# EEprom_Logger_V1.net
KiCad netlist of a schematic drawn in EAGLE
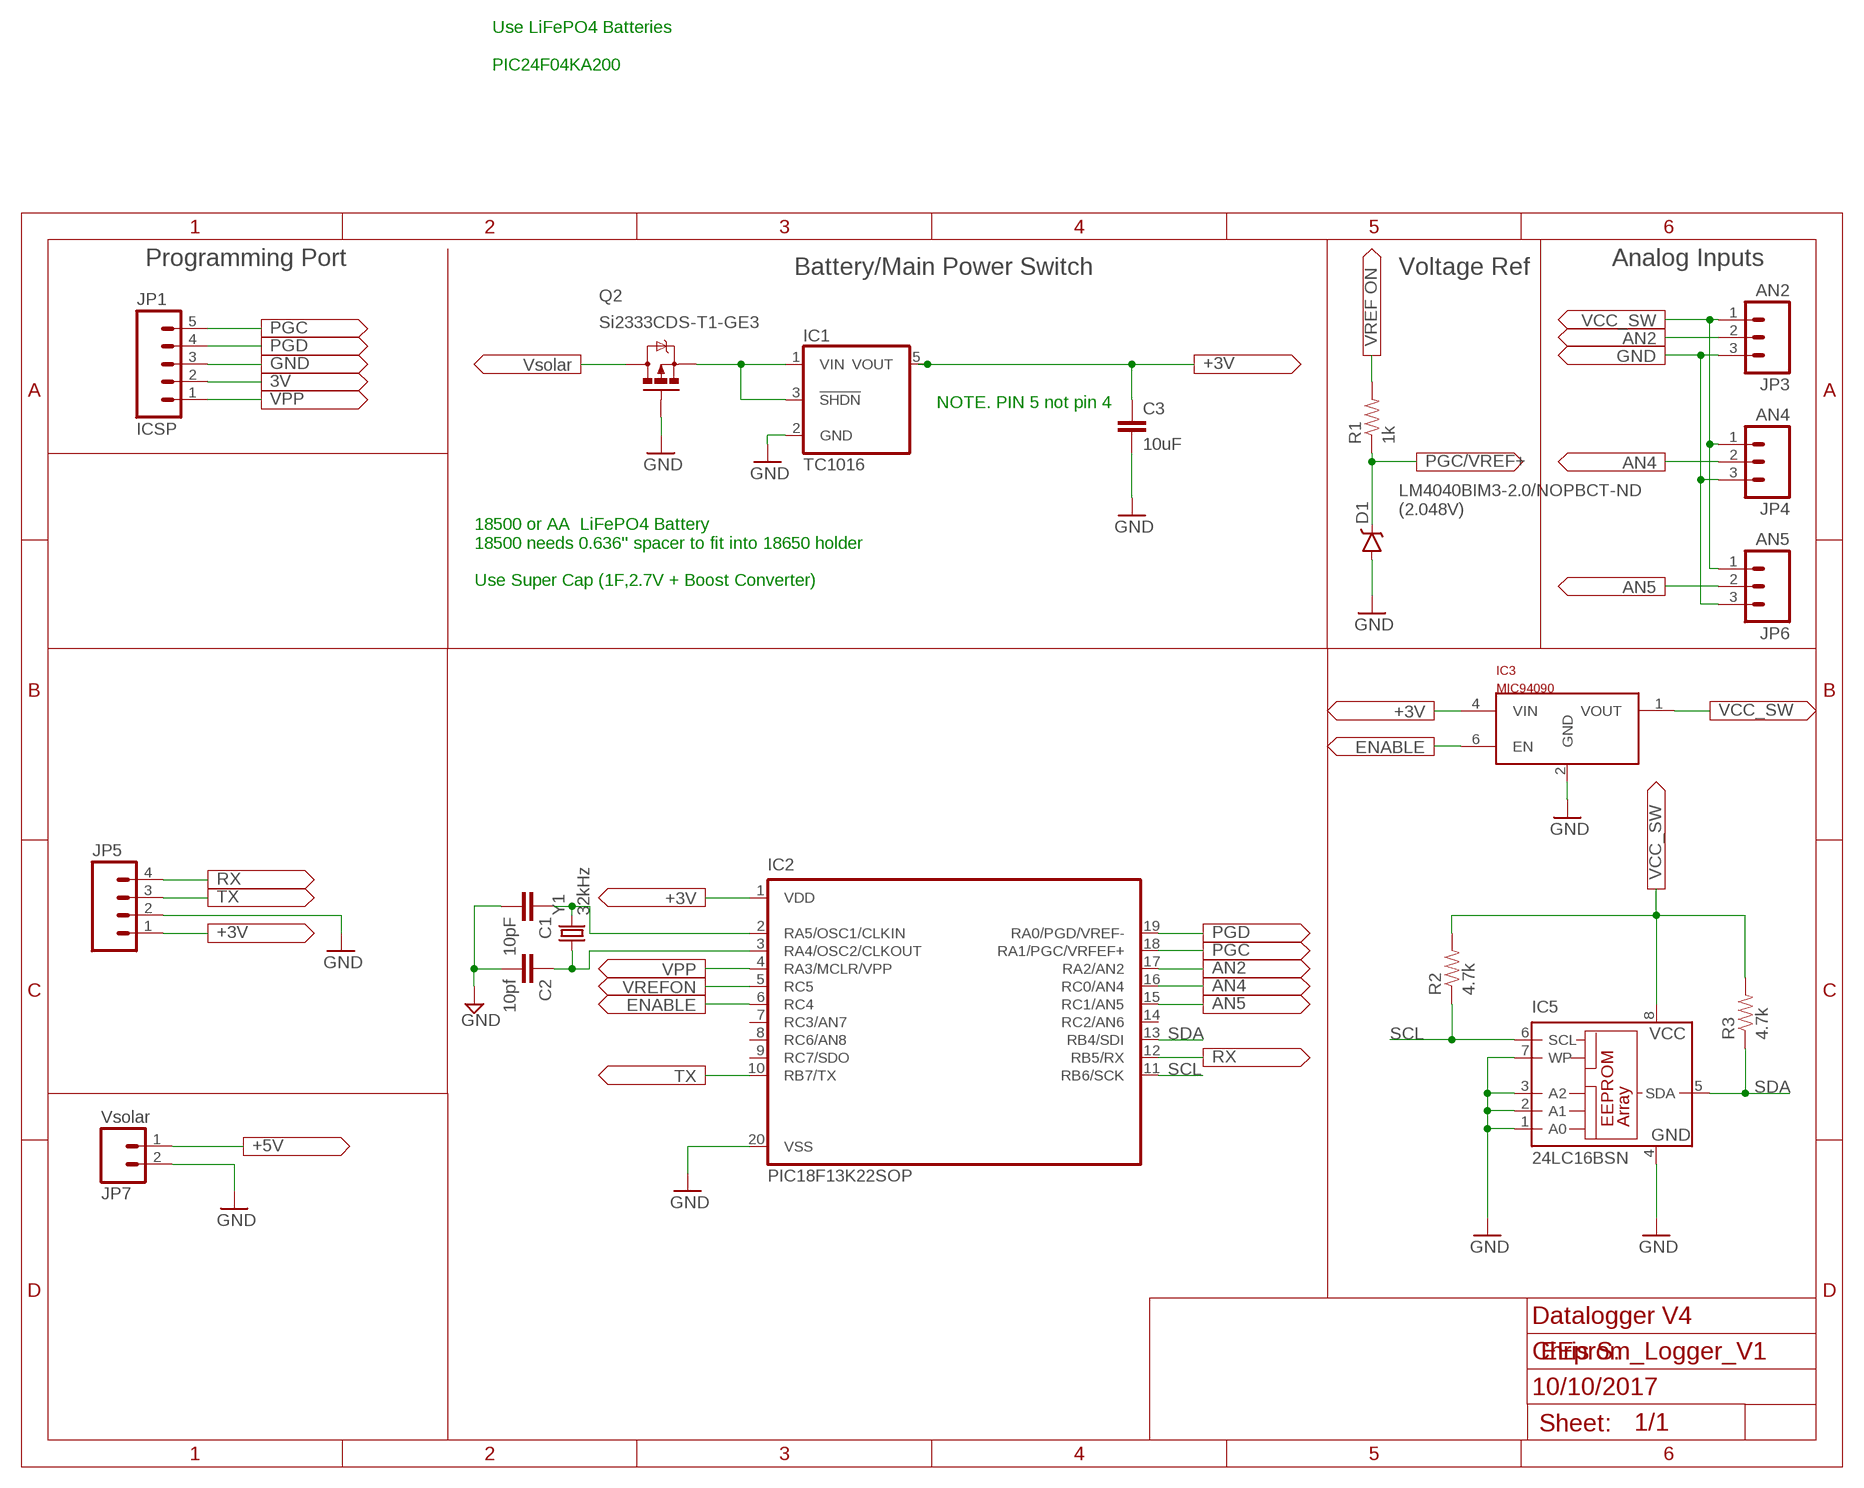
[diagram p0: schematic, sheet 1]

(export (version "E")
  (design (tool "Eeschema 10.0.6"))
  (components
    (comp (ref "C1")
      (value "10pF")
      (footprint "eagle-import:1206")
      (libsource (lib "eagle-import") (part "CAP1206"))
    )
    (comp (ref "C2")
      (value "10pf")
      (footprint "eagle-import:1206")
      (libsource (lib "eagle-import") (part "CAP1206"))
    )
    (comp (ref "C3")
      (value "10uF")
      (footprint "eagle-import:1206")
      (libsource (lib "eagle-import") (part "CAP1206"))
    )
    (comp (ref "D1")
      (value "V-REFERENCESMD")
      (footprint "eagle-import:SOT23-3")
      (libsource (lib "eagle-import") (part "V-REFERENCESMD"))
    )
    (comp (ref "IC1")
      (value "TC1016")
      (footprint "eagle-import:SOT23-5L")
      (libsource (lib "eagle-import") (part "TC1016"))
    )
    (comp (ref "IC2")
      (value "PIC18F13K22SOP")
      (footprint "eagle-import:SOP20W")
      (libsource (lib "eagle-import") (part "PIC18F13K22?SOP"))
    )
    (comp (ref "IC3")
      (value "MIC94090")
      (footprint "eagle-import:SC-70")
      (libsource (lib "eagle-import") (part "MIC94090"))
    )
    (comp (ref "IC5")
      (value "24LC16BSN")
      (footprint "eagle-import:SO-08")
      (fields (field (name "MF") "MICROCHIP") (field (name "MPN") "24LC16B/SN"))
      (libsource (lib "eagle-import") (part "24SNLC16B"))
    )
    (comp (ref "JP1")
      (value "ICSP")
      (footprint "eagle-import:1X05")
      (libsource (lib "eagle-import") (part "M05PTH"))
    )
    (comp (ref "JP3")
      (value "AN2")
      (footprint "eagle-import:JST-3-PTH")
      (libsource (lib "eagle-import") (part "M03JST-PTH"))
    )
    (comp (ref "JP4")
      (value "AN4")
      (footprint "eagle-import:JST-3-PTH")
      (libsource (lib "eagle-import") (part "M03JST-PTH"))
    )
    (comp (ref "JP5")
      (value "M04PTH")
      (footprint "eagle-import:1X04")
      (libsource (lib "eagle-import") (part "M04PTH"))
    )
    (comp (ref "JP6")
      (value "AN5")
      (footprint "eagle-import:JST-3-PTH")
      (libsource (lib "eagle-import") (part "M03JST-PTH"))
    )
    (comp (ref "JP7")
      (value "Vsolar")
      (footprint "eagle-import:JST-2-PTH")
      (libsource (lib "eagle-import") (part "M02JST-PTH-2"))
    )
    (comp (ref "Q2")
      (value "Si2333CDS-T1-GE3")
      (footprint "eagle-import:SOT23-3")
      (libsource (lib "eagle-import") (part "MOSFET-PCHANNEL"))
    )
    (comp (ref "R1")
      (value "1k")
      (footprint "eagle-import:1206")
      (libsource (lib "eagle-import") (part "RESISTOR1206"))
    )
    (comp (ref "R2")
      (value "4.7k")
      (footprint "eagle-import:1206")
      (libsource (lib "eagle-import") (part "RESISTOR1206"))
    )
    (comp (ref "R3")
      (value "4.7k")
      (footprint "eagle-import:1206")
      (libsource (lib "eagle-import") (part "RESISTOR1206"))
    )
    (comp (ref "Y1")
      (value "32kHz")
      (footprint "eagle-import:TC26V")
      (libsource (lib "eagle-import") (part "CRYSTALTC26V"))
    )
  )
  (nets
    (net (code "1") (name "/3V") (class "Default")
      (node (ref "C3") (pin "1") (pinfunction "1_1") (pintype "passive"))
      (node (ref "IC1") (pin "5") (pinfunction "VOUT_5") (pintype "passive"))
      (node (ref "IC2") (pin "1") (pinfunction "VDD_1") (pintype "power_in"))
      (node (ref "IC3") (pin "4") (pinfunction "VIN_4") (pintype "bidirectional"))
      (node (ref "JP1") (pin "2") (pinfunction "2_2") (pintype "passive"))
      (node (ref "JP5") (pin "1") (pinfunction "1_1") (pintype "passive"))
    )
    (net (code "2") (name "/AN2") (class "Default")
      (node (ref "IC2") (pin "17") (pinfunction "RA2/AN2_17") (pintype "bidirectional"))
      (node (ref "JP3") (pin "2") (pinfunction "2_2") (pintype "passive"))
    )
    (net (code "3") (name "/AN4") (class "Default")
      (node (ref "IC2") (pin "16") (pinfunction "RC0/AN4_16") (pintype "bidirectional"))
      (node (ref "JP4") (pin "2") (pinfunction "2_2") (pintype "passive"))
    )
    (net (code "4") (name "/AN5") (class "Default")
      (node (ref "IC2") (pin "15") (pinfunction "RC1/AN5_15") (pintype "bidirectional"))
      (node (ref "JP6") (pin "2") (pinfunction "2_2") (pintype "passive"))
    )
    (net (code "5") (name "/ENABLE") (class "Default")
      (node (ref "IC2") (pin "6") (pinfunction "RC4_6") (pintype "bidirectional"))
      (node (ref "IC3") (pin "6") (pinfunction "EN_6") (pintype "bidirectional"))
    )
    (net (code "6") (name "/PGC") (class "Default")
      (node (ref "D1") (pin "1") (pinfunction "C_1") (pintype "passive"))
      (node (ref "IC2") (pin "18") (pinfunction "RA1/PGC/VRFEF+_18") (pintype "bidirectional"))
      (node (ref "JP1") (pin "5") (pinfunction "5_5") (pintype "passive"))
      (node (ref "R1") (pin "1") (pinfunction "1_1") (pintype "passive"))
    )
    (net (code "7") (name "/PGD") (class "Default")
      (node (ref "IC2") (pin "19") (pinfunction "RA0/PGD/VREF-_19") (pintype "bidirectional"))
      (node (ref "JP1") (pin "4") (pinfunction "4_4") (pintype "passive"))
    )
    (net (code "8") (name "/RX") (class "Default")
      (node (ref "IC2") (pin "12") (pinfunction "RB5/RX_12") (pintype "bidirectional"))
      (node (ref "JP5") (pin "4") (pinfunction "4_4") (pintype "passive"))
    )
    (net (code "9") (name "/SCL") (class "Default")
      (node (ref "IC2") (pin "11") (pinfunction "RB6/SCK_11") (pintype "bidirectional"))
      (node (ref "IC5") (pin "6") (pinfunction "SCL_6") (pintype "input"))
      (node (ref "R2") (pin "1") (pinfunction "1_1") (pintype "passive"))
    )
    (net (code "10") (name "/SDA") (class "Default")
      (node (ref "IC2") (pin "13") (pinfunction "RB4/SDI_13") (pintype "bidirectional"))
      (node (ref "IC5") (pin "5") (pinfunction "SDA_5") (pintype "bidirectional"))
      (node (ref "R3") (pin "1") (pinfunction "1_1") (pintype "passive"))
    )
    (net (code "11") (name "/SWITCHED_VCC") (class "Default")
      (node (ref "IC3") (pin "1") (pinfunction "VOUT_1") (pintype "bidirectional"))
      (node (ref "IC5") (pin "8") (pinfunction "VCC_8") (pintype "power_in"))
      (node (ref "JP3") (pin "1") (pinfunction "1_1") (pintype "passive"))
      (node (ref "JP4") (pin "1") (pinfunction "1_1") (pintype "passive"))
      (node (ref "JP6") (pin "1") (pinfunction "1_1") (pintype "passive"))
      (node (ref "R2") (pin "2") (pinfunction "2_2") (pintype "passive"))
      (node (ref "R3") (pin "2") (pinfunction "2_2") (pintype "passive"))
    )
    (net (code "12") (name "/TX") (class "Default")
      (node (ref "IC2") (pin "10") (pinfunction "RB7/TX_10") (pintype "bidirectional"))
      (node (ref "JP5") (pin "3") (pinfunction "3_3") (pintype "passive"))
    )
    (net (code "13") (name "/VPP") (class "Default")
      (node (ref "IC2") (pin "4") (pinfunction "RA3/MCLR/VPP_4") (pintype "bidirectional"))
      (node (ref "JP1") (pin "1") (pinfunction "1_1") (pintype "passive"))
    )
    (net (code "14") (name "/VREFON") (class "Default")
      (node (ref "IC2") (pin "5") (pinfunction "RC5_5") (pintype "bidirectional"))
      (node (ref "R1") (pin "2") (pinfunction "2_2") (pintype "passive"))
    )
    (net (code "15") (name "/VSOLAR") (class "Default")
      (node (ref "JP7") (pin "1") (pinfunction "1_1") (pintype "passive"))
      (node (ref "Q2") (pin "3") (pinfunction "D_3") (pintype "passive"))
    )
    (net (code "16") (name "GND") (class "Default")
      (node (ref "C1") (pin "2") (pinfunction "2_2") (pintype "passive"))
      (node (ref "C2") (pin "2") (pinfunction "2_2") (pintype "passive"))
      (node (ref "C3") (pin "2") (pinfunction "2_2") (pintype "passive"))
      (node (ref "D1") (pin "2") (pinfunction "A_2") (pintype "passive"))
      (node (ref "IC1") (pin "2") (pinfunction "GND_2") (pintype "passive"))
      (node (ref "IC2") (pin "20") (pinfunction "VSS_20") (pintype "power_in"))
      (node (ref "IC3") (pin "2") (pinfunction "GND_2") (pintype "bidirectional"))
      (node (ref "IC5") (pin "1") (pinfunction "A0_1") (pintype "input"))
      (node (ref "IC5") (pin "2") (pinfunction "A1_2") (pintype "input"))
      (node (ref "IC5") (pin "3") (pinfunction "A2_3") (pintype "input"))
      (node (ref "IC5") (pin "4") (pinfunction "GND_4") (pintype "power_in"))
      (node (ref "IC5") (pin "7") (pinfunction "WP_7") (pintype "input"))
      (node (ref "JP1") (pin "3") (pinfunction "3_3") (pintype "passive"))
      (node (ref "JP3") (pin "3") (pinfunction "3_3") (pintype "passive"))
      (node (ref "JP4") (pin "3") (pinfunction "3_3") (pintype "passive"))
      (node (ref "JP5") (pin "2") (pinfunction "2_2") (pintype "passive"))
      (node (ref "JP6") (pin "3") (pinfunction "3_3") (pintype "passive"))
      (node (ref "JP7") (pin "2") (pinfunction "2_2") (pintype "passive"))
      (node (ref "Q2") (pin "1") (pinfunction "G_1") (pintype "passive"))
    )
    (net (code "17") (name "Net-(IC1-VIN)") (class "Default")
      (node (ref "IC1") (pin "1") (pinfunction "VIN_1") (pintype "input"))
      (node (ref "IC1") (pin "3") (pinfunction "~{SHDN}_3") (pintype "input"))
      (node (ref "Q2") (pin "2") (pinfunction "S_2") (pintype "passive"))
    )
    (net (code "18") (name "Net-(IC2-RA4{slash}OSC2{slash}CLKOUT)") (class "Default")
      (node (ref "C2") (pin "1") (pinfunction "1_1") (pintype "passive"))
      (node (ref "IC2") (pin "3") (pinfunction "RA4/OSC2/CLKOUT_3") (pintype "bidirectional"))
      (node (ref "Y1") (pin "1") (pinfunction "1_1") (pintype "passive"))
    )
    (net (code "19") (name "Net-(IC2-RA5{slash}OSC1{slash}CLKIN)") (class "Default")
      (node (ref "C1") (pin "1") (pinfunction "1_1") (pintype "passive"))
      (node (ref "IC2") (pin "2") (pinfunction "RA5/OSC1/CLKIN_2") (pintype "bidirectional"))
      (node (ref "Y1") (pin "2") (pinfunction "2_2") (pintype "passive"))
    )
    (net (code "20") (name "unconnected-(IC2-RC2{slash}AN6-Pad14)") (class "Default")
      (node (ref "IC2") (pin "14") (pinfunction "RC2/AN6_14") (pintype "bidirectional"))
    )
    (net (code "21") (name "unconnected-(IC2-RC3{slash}AN7-Pad7)") (class "Default")
      (node (ref "IC2") (pin "7") (pinfunction "RC3/AN7_7") (pintype "bidirectional"))
    )
    (net (code "22") (name "unconnected-(IC2-RC6{slash}AN8-Pad8)") (class "Default")
      (node (ref "IC2") (pin "8") (pinfunction "RC6/AN8_8") (pintype "bidirectional"))
    )
    (net (code "23") (name "unconnected-(IC2-RC7{slash}SDO-Pad9)") (class "Default")
      (node (ref "IC2") (pin "9") (pinfunction "RC7/SDO_9") (pintype "bidirectional"))
    )
  )
)
